# MEASUREMENT.net
KiCad netlist of a schematic drawn in Altium Designer
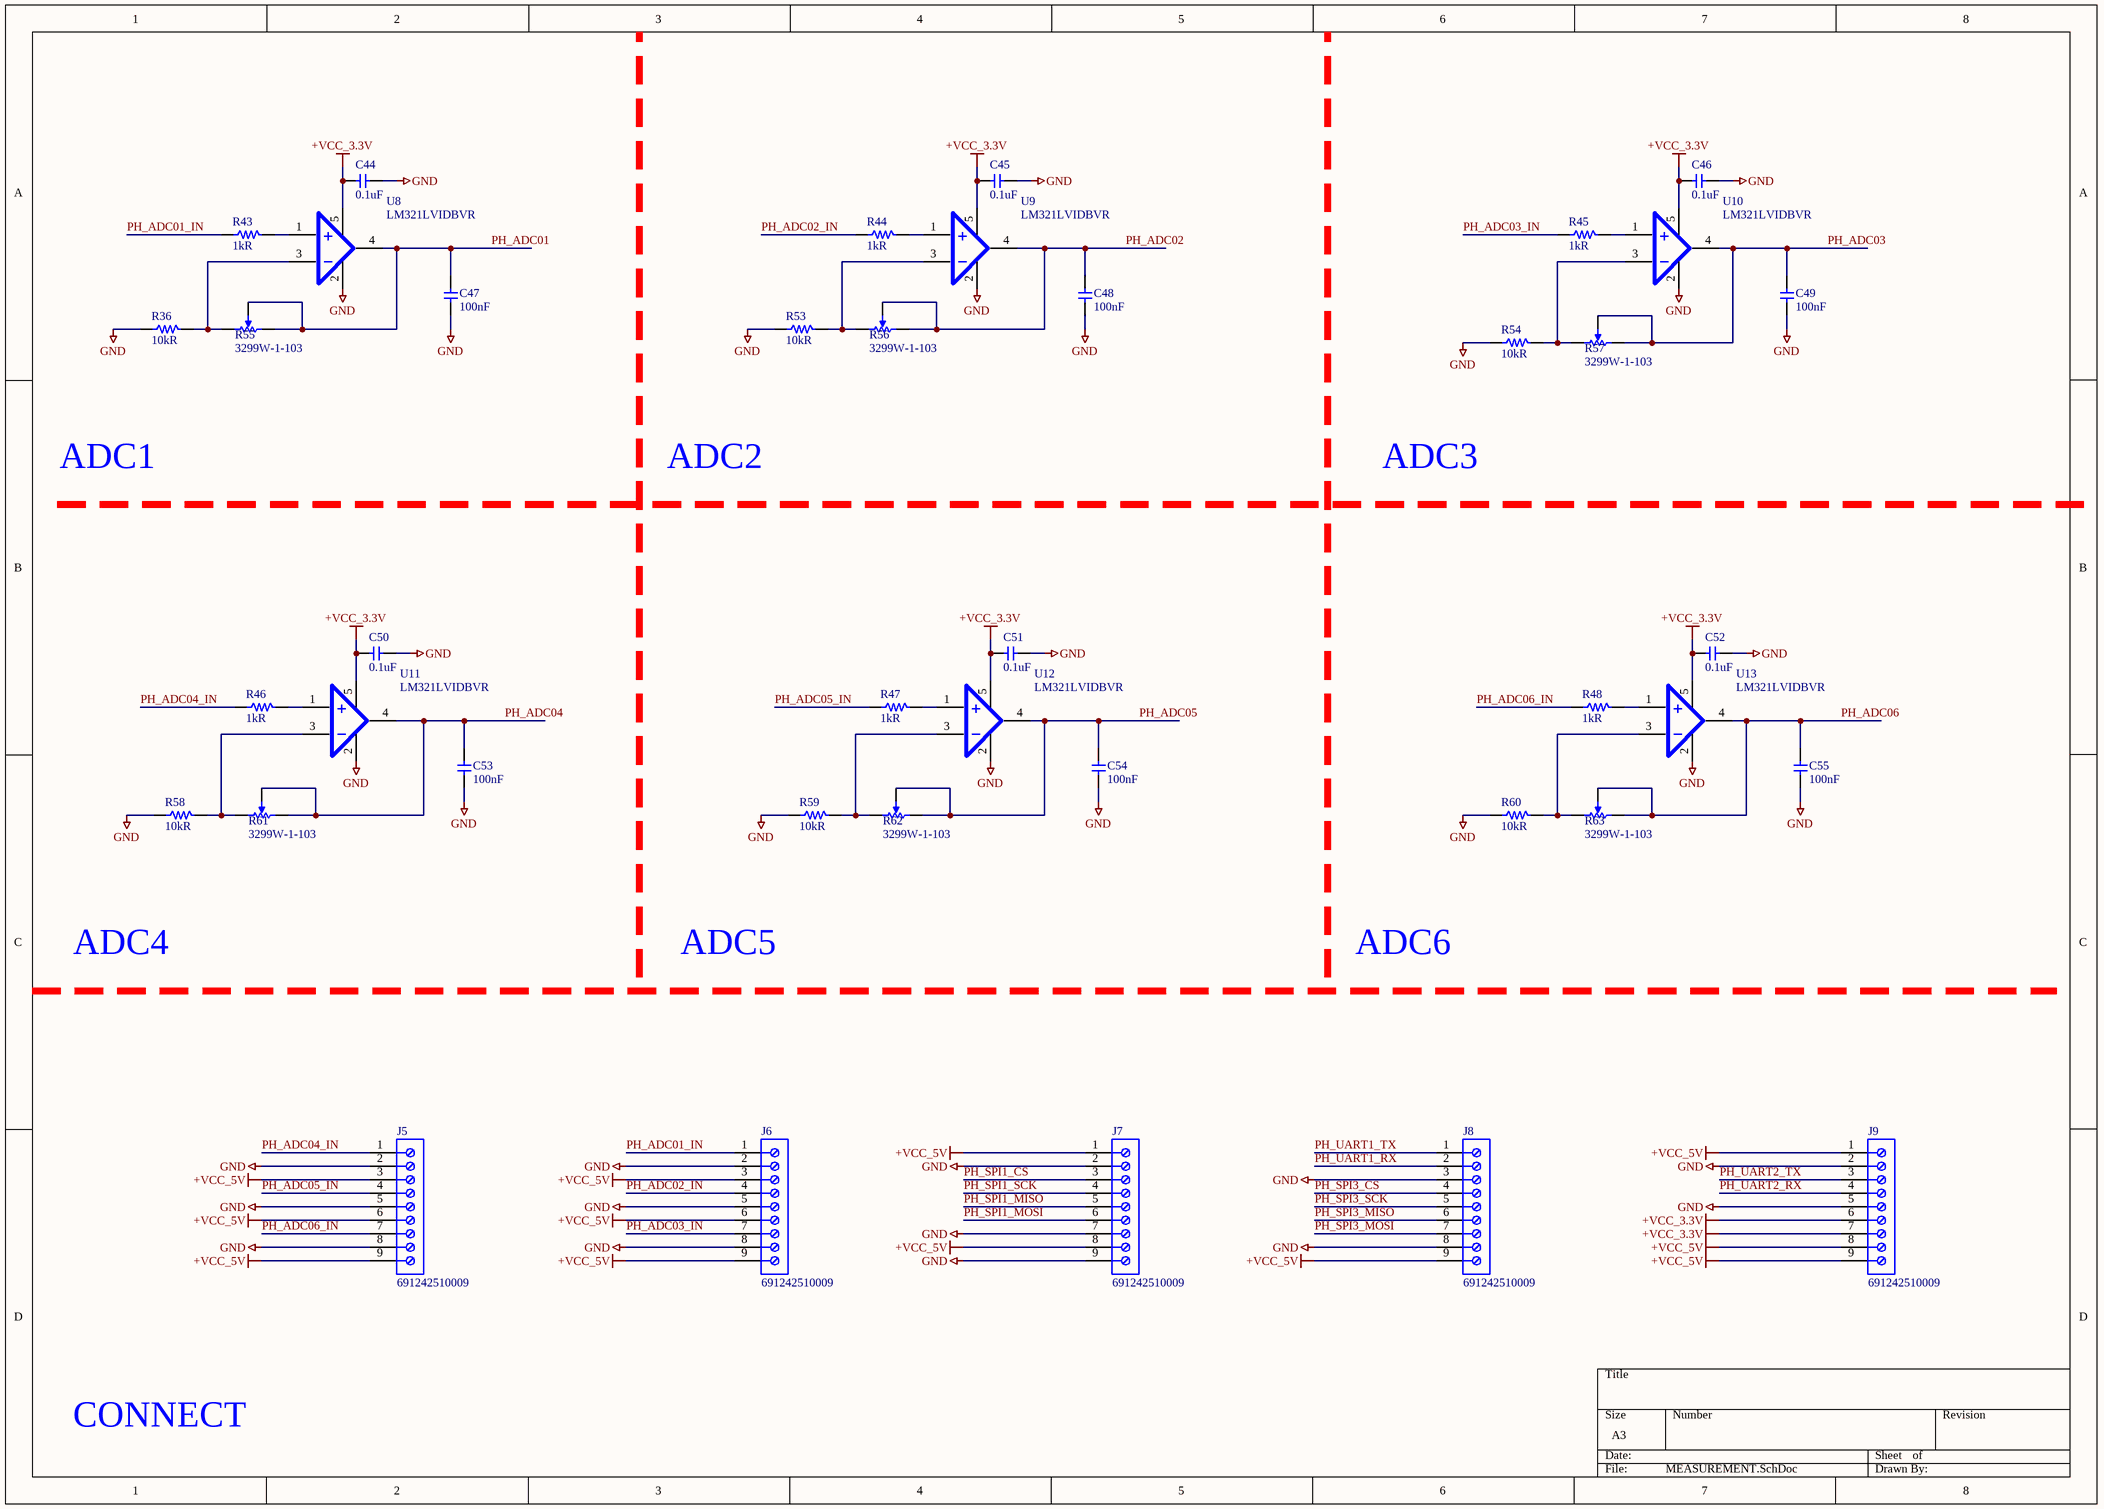
[diagram p0: MEASUREMENT.SchDoc]

(export (version "E")
  (design (tool "Eeschema 10.0.6"))
  (components
    (comp (ref "C44")
      (value "0.1uF")
      (footprint "CAP 0402 (1005)")
      (description "50V 100nF ±10% 0402 Multilayer Ceramic Capacitors MLCC - SMD/SMT ROHS")
      (fields
        (field (name "MANUFACTURER") "Samwha Capacitor")
        (field (name "MANUFACTURER PART NUMBER") "CS1005X7R104K500NR")
      )
      (libsource (lib "BSR NODE_V2.0 LIB") (part "CAP0402 0.1uF 50V"))
    )
    (comp (ref "C45")
      (value "0.1uF")
      (footprint "CAP 0402 (1005)")
      (description "50V 100nF ±10% 0402 Multilayer Ceramic Capacitors MLCC - SMD/SMT ROHS")
      (fields
        (field (name "MANUFACTURER") "Samwha Capacitor")
        (field (name "MANUFACTURER PART NUMBER") "CS1005X7R104K500NR")
      )
      (libsource (lib "BSR NODE_V2.0 LIB") (part "CAP0402 0.1uF 50V"))
    )
    (comp (ref "C46")
      (value "0.1uF")
      (footprint "CAP 0402 (1005)")
      (description "50V 100nF ±10% 0402 Multilayer Ceramic Capacitors MLCC - SMD/SMT ROHS")
      (fields
        (field (name "MANUFACTURER") "Samwha Capacitor")
        (field (name "MANUFACTURER PART NUMBER") "CS1005X7R104K500NR")
      )
      (libsource (lib "BSR NODE_V2.0 LIB") (part "CAP0402 0.1uF 50V"))
    )
    (comp (ref "C47")
      (value "100nF")
      (footprint "CAP 0402 (1005)")
      (description "50V 100nF ±10% 0402 Multilayer Ceramic Capacitors MLCC - SMD/SMT ROHS")
      (fields
        (field (name "MANUFACTURER") "Samwha Capacitor")
        (field (name "MANUFACTURER PART NUMBER") "CS1005X7R104K500NR")
      )
      (libsource (lib "BSR NODE_V2.0 LIB") (part "CAP0402 0.1uF 50V"))
    )
    (comp (ref "C48")
      (value "100nF")
      (footprint "CAP 0402 (1005)")
      (description "50V 100nF ±10% 0402 Multilayer Ceramic Capacitors MLCC - SMD/SMT ROHS")
      (fields
        (field (name "MANUFACTURER") "Samwha Capacitor")
        (field (name "MANUFACTURER PART NUMBER") "CS1005X7R104K500NR")
      )
      (libsource (lib "BSR NODE_V2.0 LIB") (part "CAP0402 0.1uF 50V"))
    )
    (comp (ref "C49")
      (value "100nF")
      (footprint "CAP 0402 (1005)")
      (description "50V 100nF ±10% 0402 Multilayer Ceramic Capacitors MLCC - SMD/SMT ROHS")
      (fields
        (field (name "MANUFACTURER") "Samwha Capacitor")
        (field (name "MANUFACTURER PART NUMBER") "CS1005X7R104K500NR")
      )
      (libsource (lib "BSR NODE_V2.0 LIB") (part "CAP0402 0.1uF 50V"))
    )
    (comp (ref "C50")
      (value "0.1uF")
      (footprint "CAP 0402 (1005)")
      (description "50V 100nF ±10% 0402 Multilayer Ceramic Capacitors MLCC - SMD/SMT ROHS")
      (fields
        (field (name "MANUFACTURER") "Samwha Capacitor")
        (field (name "MANUFACTURER PART NUMBER") "CS1005X7R104K500NR")
      )
      (libsource (lib "BSR NODE_V2.0 LIB") (part "CAP0402 0.1uF 50V"))
    )
    (comp (ref "C51")
      (value "0.1uF")
      (footprint "CAP 0402 (1005)")
      (description "50V 100nF ±10% 0402 Multilayer Ceramic Capacitors MLCC - SMD/SMT ROHS")
      (fields
        (field (name "MANUFACTURER") "Samwha Capacitor")
        (field (name "MANUFACTURER PART NUMBER") "CS1005X7R104K500NR")
      )
      (libsource (lib "BSR NODE_V2.0 LIB") (part "CAP0402 0.1uF 50V"))
    )
    (comp (ref "C52")
      (value "0.1uF")
      (footprint "CAP 0402 (1005)")
      (description "50V 100nF ±10% 0402 Multilayer Ceramic Capacitors MLCC - SMD/SMT ROHS")
      (fields
        (field (name "MANUFACTURER") "Samwha Capacitor")
        (field (name "MANUFACTURER PART NUMBER") "CS1005X7R104K500NR")
      )
      (libsource (lib "BSR NODE_V2.0 LIB") (part "CAP0402 0.1uF 50V"))
    )
    (comp (ref "C53")
      (value "100nF")
      (footprint "CAP 0402 (1005)")
      (description "50V 100nF ±10% 0402 Multilayer Ceramic Capacitors MLCC - SMD/SMT ROHS")
      (fields
        (field (name "MANUFACTURER") "Samwha Capacitor")
        (field (name "MANUFACTURER PART NUMBER") "CS1005X7R104K500NR")
      )
      (libsource (lib "BSR NODE_V2.0 LIB") (part "CAP0402 0.1uF 50V"))
    )
    (comp (ref "C54")
      (value "100nF")
      (footprint "CAP 0402 (1005)")
      (description "50V 100nF ±10% 0402 Multilayer Ceramic Capacitors MLCC - SMD/SMT ROHS")
      (fields
        (field (name "MANUFACTURER") "Samwha Capacitor")
        (field (name "MANUFACTURER PART NUMBER") "CS1005X7R104K500NR")
      )
      (libsource (lib "BSR NODE_V2.0 LIB") (part "CAP0402 0.1uF 50V"))
    )
    (comp (ref "C55")
      (value "100nF")
      (footprint "CAP 0402 (1005)")
      (description "50V 100nF ±10% 0402 Multilayer Ceramic Capacitors MLCC - SMD/SMT ROHS")
      (fields
        (field (name "MANUFACTURER") "Samwha Capacitor")
        (field (name "MANUFACTURER PART NUMBER") "CS1005X7R104K500NR")
      )
      (libsource (lib "BSR NODE_V2.0 LIB") (part "CAP0402 0.1uF 50V"))
    )
    (comp (ref "J5")
      (value "691242510009")
      (footprint "691242510009")
      (description "Terminal Block, 5.08MM Pitch, Horizontal, Rising Cage Clamp, 12-30 AWG, 9 Pin")
      (libsource (lib "Altium Content Vault") (part "TBL - 1R - 09P - Screw"))
    )
    (comp (ref "J6")
      (value "691242510009")
      (footprint "691242510009")
      (description "Terminal Block, 5.08MM Pitch, Horizontal, Rising Cage Clamp, 12-30 AWG, 9 Pin")
      (libsource (lib "Altium Content Vault") (part "TBL - 1R - 09P - Screw"))
    )
    (comp (ref "J7")
      (value "691242510009")
      (footprint "691242510009")
      (description "Terminal Block, 5.08MM Pitch, Horizontal, Rising Cage Clamp, 12-30 AWG, 9 Pin")
      (libsource (lib "Altium Content Vault") (part "TBL - 1R - 09P - Screw"))
    )
    (comp (ref "J8")
      (value "691242510009")
      (footprint "691242510009")
      (description "Terminal Block, 5.08MM Pitch, Horizontal, Rising Cage Clamp, 12-30 AWG, 9 Pin")
      (libsource (lib "Altium Content Vault") (part "TBL - 1R - 09P - Screw"))
    )
    (comp (ref "J9")
      (value "691242510009")
      (footprint "691242510009")
      (description "Terminal Block, 5.08MM Pitch, Horizontal, Rising Cage Clamp, 12-30 AWG, 9 Pin")
      (libsource (lib "Altium Content Vault") (part "TBL - 1R - 09P - Screw"))
    )
    (comp (ref "R36")
      (value "10kR")
      (footprint "RES 0402 (1005)")
      (description "±1% 10kΩ 0402 Chip Resistor - Surface Mount ROHS")
      (fields (field (name "MANUFACTURER") "VO") (field (name "MANUFACTURER PART NUMBER") "SCR0402F10K"))
      (libsource (lib "BSR NODE_V2.0 LIB") (part "RES0402 10kR 1%"))
    )
    (comp (ref "R43")
      (value "1kR")
      (footprint "RES 0402 (1005)")
      (description "±1% 10kΩ 0402 Chip Resistor - Surface Mount ROHS")
      (fields (field (name "MANUFACTURER") "VO") (field (name "MANUFACTURER PART NUMBER") "SCR0402F10K"))
      (libsource (lib "BSR NODE_V2.0 LIB") (part "RES0402 10kR 1%"))
    )
    (comp (ref "R44")
      (value "1kR")
      (footprint "RES 0402 (1005)")
      (description "±1% 10kΩ 0402 Chip Resistor - Surface Mount ROHS")
      (fields (field (name "MANUFACTURER") "VO") (field (name "MANUFACTURER PART NUMBER") "SCR0402F10K"))
      (libsource (lib "BSR NODE_V2.0 LIB") (part "RES0402 10kR 1%"))
    )
    (comp (ref "R45")
      (value "1kR")
      (footprint "RES 0402 (1005)")
      (description "±1% 10kΩ 0402 Chip Resistor - Surface Mount ROHS")
      (fields (field (name "MANUFACTURER") "VO") (field (name "MANUFACTURER PART NUMBER") "SCR0402F10K"))
      (libsource (lib "BSR NODE_V2.0 LIB") (part "RES0402 10kR 1%"))
    )
    (comp (ref "R46")
      (value "1kR")
      (footprint "RES 0402 (1005)")
      (description "±1% 10kΩ 0402 Chip Resistor - Surface Mount ROHS")
      (fields (field (name "MANUFACTURER") "VO") (field (name "MANUFACTURER PART NUMBER") "SCR0402F10K"))
      (libsource (lib "BSR NODE_V2.0 LIB") (part "RES0402 10kR 1%"))
    )
    (comp (ref "R47")
      (value "1kR")
      (footprint "RES 0402 (1005)")
      (description "±1% 10kΩ 0402 Chip Resistor - Surface Mount ROHS")
      (fields (field (name "MANUFACTURER") "VO") (field (name "MANUFACTURER PART NUMBER") "SCR0402F10K"))
      (libsource (lib "BSR NODE_V2.0 LIB") (part "RES0402 10kR 1%"))
    )
    (comp (ref "R48")
      (value "1kR")
      (footprint "RES 0402 (1005)")
      (description "±1% 10kΩ 0402 Chip Resistor - Surface Mount ROHS")
      (fields (field (name "MANUFACTURER") "VO") (field (name "MANUFACTURER PART NUMBER") "SCR0402F10K"))
      (libsource (lib "BSR NODE_V2.0 LIB") (part "RES0402 10kR 1%"))
    )
    (comp (ref "R53")
      (value "10kR")
      (footprint "RES 0402 (1005)")
      (description "±1% 10kΩ 0402 Chip Resistor - Surface Mount ROHS")
      (fields (field (name "MANUFACTURER") "VO") (field (name "MANUFACTURER PART NUMBER") "SCR0402F10K"))
      (libsource (lib "BSR NODE_V2.0 LIB") (part "RES0402 10kR 1%"))
    )
    (comp (ref "R54")
      (value "10kR")
      (footprint "RES 0402 (1005)")
      (description "±1% 10kΩ 0402 Chip Resistor - Surface Mount ROHS")
      (fields (field (name "MANUFACTURER") "VO") (field (name "MANUFACTURER PART NUMBER") "SCR0402F10K"))
      (libsource (lib "BSR NODE_V2.0 LIB") (part "RES0402 10kR 1%"))
    )
    (comp (ref "R55")
      (value "3299W-1-103")
      (footprint "BOUR-3299W-3_V")
      (fields (field (name "MANUFACTURER") "Bourns") (field (name "TOLERANCE") "10%"))
      (libsource (lib "Altium Content Vault") (part "RES-ADJ-3_A"))
    )
    (comp (ref "R56")
      (value "3299W-1-103")
      (footprint "BOUR-3299W-3_V")
      (fields (field (name "MANUFACTURER") "Bourns") (field (name "TOLERANCE") "10%"))
      (libsource (lib "Altium Content Vault") (part "RES-ADJ-3_A"))
    )
    (comp (ref "R57")
      (value "3299W-1-103")
      (footprint "BOUR-3299W-3_V")
      (fields (field (name "MANUFACTURER") "Bourns") (field (name "TOLERANCE") "10%"))
      (libsource (lib "Altium Content Vault") (part "RES-ADJ-3_A"))
    )
    (comp (ref "R58")
      (value "10kR")
      (footprint "RES 0402 (1005)")
      (description "±1% 10kΩ 0402 Chip Resistor - Surface Mount ROHS")
      (fields (field (name "MANUFACTURER") "VO") (field (name "MANUFACTURER PART NUMBER") "SCR0402F10K"))
      (libsource (lib "BSR NODE_V2.0 LIB") (part "RES0402 10kR 1%"))
    )
    (comp (ref "R59")
      (value "10kR")
      (footprint "RES 0402 (1005)")
      (description "±1% 10kΩ 0402 Chip Resistor - Surface Mount ROHS")
      (fields (field (name "MANUFACTURER") "VO") (field (name "MANUFACTURER PART NUMBER") "SCR0402F10K"))
      (libsource (lib "BSR NODE_V2.0 LIB") (part "RES0402 10kR 1%"))
    )
    (comp (ref "R60")
      (value "10kR")
      (footprint "RES 0402 (1005)")
      (description "±1% 10kΩ 0402 Chip Resistor - Surface Mount ROHS")
      (fields (field (name "MANUFACTURER") "VO") (field (name "MANUFACTURER PART NUMBER") "SCR0402F10K"))
      (libsource (lib "BSR NODE_V2.0 LIB") (part "RES0402 10kR 1%"))
    )
    (comp (ref "R61")
      (value "3299W-1-103")
      (footprint "BOUR-3299W-3_V")
      (fields (field (name "MANUFACTURER") "Bourns") (field (name "TOLERANCE") "10%"))
      (libsource (lib "Altium Content Vault") (part "RES-ADJ-3_A"))
    )
    (comp (ref "R62")
      (value "3299W-1-103")
      (footprint "BOUR-3299W-3_V")
      (fields (field (name "MANUFACTURER") "Bourns") (field (name "TOLERANCE") "10%"))
      (libsource (lib "Altium Content Vault") (part "RES-ADJ-3_A"))
    )
    (comp (ref "R63")
      (value "3299W-1-103")
      (footprint "BOUR-3299W-3_V")
      (fields (field (name "MANUFACTURER") "Bourns") (field (name "TOLERANCE") "10%"))
      (libsource (lib "Altium Content Vault") (part "RES-ADJ-3_A"))
    )
    (comp (ref "U8")
      (value "LM321LVIDBVR")
      (footprint "SOT-23-5")
      (description "IC OPAMP GP 1 CIRCUIT SOT23-5")
      (fields (field (name "MANUFACTURER") "Texas Instruments"))
      (libsource (lib "BSR") (part "IC OPAM LM321LVIDBVR"))
    )
    (comp (ref "U9")
      (value "LM321LVIDBVR")
      (footprint "SOT-23-5")
      (description "IC OPAMP GP 1 CIRCUIT SOT23-5")
      (fields (field (name "MANUFACTURER") "Texas Instruments"))
      (libsource (lib "BSR") (part "IC OPAM LM321LVIDBVR"))
    )
    (comp (ref "U10")
      (value "LM321LVIDBVR")
      (footprint "SOT-23-5")
      (description "IC OPAMP GP 1 CIRCUIT SOT23-5")
      (fields (field (name "MANUFACTURER") "Texas Instruments"))
      (libsource (lib "BSR") (part "IC OPAM LM321LVIDBVR"))
    )
    (comp (ref "U11")
      (value "LM321LVIDBVR")
      (footprint "SOT-23-5")
      (description "IC OPAMP GP 1 CIRCUIT SOT23-5")
      (fields (field (name "MANUFACTURER") "Texas Instruments"))
      (libsource (lib "BSR") (part "IC OPAM LM321LVIDBVR"))
    )
    (comp (ref "U12")
      (value "LM321LVIDBVR")
      (footprint "SOT-23-5")
      (description "IC OPAMP GP 1 CIRCUIT SOT23-5")
      (fields (field (name "MANUFACTURER") "Texas Instruments"))
      (libsource (lib "BSR") (part "IC OPAM LM321LVIDBVR"))
    )
    (comp (ref "U13")
      (value "LM321LVIDBVR")
      (footprint "SOT-23-5")
      (description "IC OPAMP GP 1 CIRCUIT SOT23-5")
      (fields (field (name "MANUFACTURER") "Texas Instruments"))
      (libsource (lib "BSR") (part "IC OPAM LM321LVIDBVR"))
    )
  )
  (nets
    (net (code "1") (name "+VCC_3.3V") (class "Default")
      (node (ref "C44") (pin "2") (pinfunction "2_2") (pintype "passive"))
      (node (ref "C45") (pin "2") (pinfunction "2_2") (pintype "passive"))
      (node (ref "C46") (pin "2") (pinfunction "2_2") (pintype "passive"))
      (node (ref "C50") (pin "2") (pinfunction "2_2") (pintype "passive"))
      (node (ref "C51") (pin "2") (pinfunction "2_2") (pintype "passive"))
      (node (ref "C52") (pin "2") (pinfunction "2_2") (pintype "passive"))
      (node (ref "J9") (pin "6") (pinfunction "6_6") (pintype "passive"))
      (node (ref "J9") (pin "7") (pinfunction "7_7") (pintype "passive"))
      (node (ref "U10") (pin "5") (pinfunction "5_5") (pintype "passive"))
      (node (ref "U11") (pin "5") (pinfunction "5_5") (pintype "passive"))
      (node (ref "U12") (pin "5") (pinfunction "5_5") (pintype "passive"))
      (node (ref "U13") (pin "5") (pinfunction "5_5") (pintype "passive"))
      (node (ref "U8") (pin "5") (pinfunction "5_5") (pintype "passive"))
      (node (ref "U9") (pin "5") (pinfunction "5_5") (pintype "passive"))
    )
    (net (code "2") (name "+VCC_5V") (class "Default")
      (node (ref "J5") (pin "3") (pinfunction "3_3") (pintype "passive"))
      (node (ref "J5") (pin "6") (pinfunction "6_6") (pintype "passive"))
      (node (ref "J5") (pin "9") (pinfunction "9_9") (pintype "passive"))
      (node (ref "J6") (pin "3") (pinfunction "3_3") (pintype "passive"))
      (node (ref "J6") (pin "6") (pinfunction "6_6") (pintype "passive"))
      (node (ref "J6") (pin "9") (pinfunction "9_9") (pintype "passive"))
      (node (ref "J7") (pin "1") (pinfunction "1_1") (pintype "passive"))
      (node (ref "J7") (pin "8") (pinfunction "8_8") (pintype "passive"))
      (node (ref "J8") (pin "9") (pinfunction "9_9") (pintype "passive"))
      (node (ref "J9") (pin "1") (pinfunction "1_1") (pintype "passive"))
      (node (ref "J9") (pin "8") (pinfunction "8_8") (pintype "passive"))
      (node (ref "J9") (pin "9") (pinfunction "9_9") (pintype "passive"))
    )
    (net (code "3") (name "/PH_ADC01") (class "Default")
      (node (ref "C47") (pin "2") (pinfunction "2_2") (pintype "passive"))
      (node (ref "R55") (pin "1") (pinfunction "1_1") (pintype "passive"))
      (node (ref "R55") (pin "2") (pinfunction "2_2") (pintype "passive"))
      (node (ref "U8") (pin "4") (pinfunction "4_4") (pintype "passive"))
    )
    (net (code "4") (name "/PH_ADC01_IN") (class "Default")
      (node (ref "J6") (pin "1") (pinfunction "1_1") (pintype "passive"))
      (node (ref "R43") (pin "2") (pinfunction "2_2") (pintype "passive"))
    )
    (net (code "5") (name "/PH_ADC02") (class "Default")
      (node (ref "C48") (pin "2") (pinfunction "2_2") (pintype "passive"))
      (node (ref "R56") (pin "1") (pinfunction "1_1") (pintype "passive"))
      (node (ref "R56") (pin "2") (pinfunction "2_2") (pintype "passive"))
      (node (ref "U9") (pin "4") (pinfunction "4_4") (pintype "passive"))
    )
    (net (code "6") (name "/PH_ADC02_IN") (class "Default")
      (node (ref "J6") (pin "4") (pinfunction "4_4") (pintype "passive"))
      (node (ref "R44") (pin "2") (pinfunction "2_2") (pintype "passive"))
    )
    (net (code "7") (name "/PH_ADC03") (class "Default")
      (node (ref "C49") (pin "2") (pinfunction "2_2") (pintype "passive"))
      (node (ref "R57") (pin "1") (pinfunction "1_1") (pintype "passive"))
      (node (ref "R57") (pin "2") (pinfunction "2_2") (pintype "passive"))
      (node (ref "U10") (pin "4") (pinfunction "4_4") (pintype "passive"))
    )
    (net (code "8") (name "/PH_ADC03_IN") (class "Default")
      (node (ref "J6") (pin "7") (pinfunction "7_7") (pintype "passive"))
      (node (ref "R45") (pin "2") (pinfunction "2_2") (pintype "passive"))
    )
    (net (code "9") (name "/PH_ADC04") (class "Default")
      (node (ref "C53") (pin "2") (pinfunction "2_2") (pintype "passive"))
      (node (ref "R61") (pin "1") (pinfunction "1_1") (pintype "passive"))
      (node (ref "R61") (pin "2") (pinfunction "2_2") (pintype "passive"))
      (node (ref "U11") (pin "4") (pinfunction "4_4") (pintype "passive"))
    )
    (net (code "10") (name "/PH_ADC04_IN") (class "Default")
      (node (ref "J5") (pin "1") (pinfunction "1_1") (pintype "passive"))
      (node (ref "R46") (pin "2") (pinfunction "2_2") (pintype "passive"))
    )
    (net (code "11") (name "/PH_ADC05") (class "Default")
      (node (ref "C54") (pin "2") (pinfunction "2_2") (pintype "passive"))
      (node (ref "R62") (pin "1") (pinfunction "1_1") (pintype "passive"))
      (node (ref "R62") (pin "2") (pinfunction "2_2") (pintype "passive"))
      (node (ref "U12") (pin "4") (pinfunction "4_4") (pintype "passive"))
    )
    (net (code "12") (name "/PH_ADC05_IN") (class "Default")
      (node (ref "J5") (pin "4") (pinfunction "4_4") (pintype "passive"))
      (node (ref "R47") (pin "2") (pinfunction "2_2") (pintype "passive"))
    )
    (net (code "13") (name "/PH_ADC06") (class "Default")
      (node (ref "C55") (pin "2") (pinfunction "2_2") (pintype "passive"))
      (node (ref "R63") (pin "1") (pinfunction "1_1") (pintype "passive"))
      (node (ref "R63") (pin "2") (pinfunction "2_2") (pintype "passive"))
      (node (ref "U13") (pin "4") (pinfunction "4_4") (pintype "passive"))
    )
    (net (code "14") (name "/PH_ADC06_IN") (class "Default")
      (node (ref "J5") (pin "7") (pinfunction "7_7") (pintype "passive"))
      (node (ref "R48") (pin "2") (pinfunction "2_2") (pintype "passive"))
    )
    (net (code "15") (name "/PH_SPI1_CS") (class "Default")
      (node (ref "J7") (pin "3") (pinfunction "3_3") (pintype "passive"))
    )
    (net (code "16") (name "/PH_SPI1_MISO") (class "Default")
      (node (ref "J7") (pin "5") (pinfunction "5_5") (pintype "passive"))
    )
    (net (code "17") (name "/PH_SPI1_MOSI") (class "Default")
      (node (ref "J7") (pin "6") (pinfunction "6_6") (pintype "passive"))
    )
    (net (code "18") (name "/PH_SPI1_SCK") (class "Default")
      (node (ref "J7") (pin "4") (pinfunction "4_4") (pintype "passive"))
    )
    (net (code "19") (name "/PH_SPI3_CS") (class "Default")
      (node (ref "J8") (pin "4") (pinfunction "4_4") (pintype "passive"))
    )
    (net (code "20") (name "/PH_SPI3_MISO") (class "Default")
      (node (ref "J8") (pin "6") (pinfunction "6_6") (pintype "passive"))
    )
    (net (code "21") (name "/PH_SPI3_MOSI") (class "Default")
      (node (ref "J8") (pin "7") (pinfunction "7_7") (pintype "passive"))
    )
    (net (code "22") (name "/PH_SPI3_SCK") (class "Default")
      (node (ref "J8") (pin "5") (pinfunction "5_5") (pintype "passive"))
    )
    (net (code "23") (name "/PH_UART1_RX") (class "Default")
      (node (ref "J8") (pin "2") (pinfunction "2_2") (pintype "passive"))
    )
    (net (code "24") (name "/PH_UART1_TX") (class "Default")
      (node (ref "J8") (pin "1") (pinfunction "1_1") (pintype "passive"))
    )
    (net (code "25") (name "/PH_UART2_RX") (class "Default")
      (node (ref "J9") (pin "4") (pinfunction "4_4") (pintype "passive"))
    )
    (net (code "26") (name "/PH_UART2_TX") (class "Default")
      (node (ref "J9") (pin "3") (pinfunction "3_3") (pintype "passive"))
    )
    (net (code "27") (name "GND") (class "Default")
      (node (ref "C44") (pin "1") (pinfunction "1_1") (pintype "passive"))
      (node (ref "C45") (pin "1") (pinfunction "1_1") (pintype "passive"))
      (node (ref "C46") (pin "1") (pinfunction "1_1") (pintype "passive"))
      (node (ref "C47") (pin "1") (pinfunction "1_1") (pintype "passive"))
      (node (ref "C48") (pin "1") (pinfunction "1_1") (pintype "passive"))
      (node (ref "C49") (pin "1") (pinfunction "1_1") (pintype "passive"))
      (node (ref "C50") (pin "1") (pinfunction "1_1") (pintype "passive"))
      (node (ref "C51") (pin "1") (pinfunction "1_1") (pintype "passive"))
      (node (ref "C52") (pin "1") (pinfunction "1_1") (pintype "passive"))
      (node (ref "C53") (pin "1") (pinfunction "1_1") (pintype "passive"))
      (node (ref "C54") (pin "1") (pinfunction "1_1") (pintype "passive"))
      (node (ref "C55") (pin "1") (pinfunction "1_1") (pintype "passive"))
      (node (ref "J5") (pin "2") (pinfunction "2_2") (pintype "passive"))
      (node (ref "J5") (pin "5") (pinfunction "5_5") (pintype "passive"))
      (node (ref "J5") (pin "8") (pinfunction "8_8") (pintype "passive"))
      (node (ref "J6") (pin "2") (pinfunction "2_2") (pintype "passive"))
      (node (ref "J6") (pin "5") (pinfunction "5_5") (pintype "passive"))
      (node (ref "J6") (pin "8") (pinfunction "8_8") (pintype "passive"))
      (node (ref "J7") (pin "2") (pinfunction "2_2") (pintype "passive"))
      (node (ref "J7") (pin "7") (pinfunction "7_7") (pintype "passive"))
      (node (ref "J7") (pin "9") (pinfunction "9_9") (pintype "passive"))
      (node (ref "J8") (pin "3") (pinfunction "3_3") (pintype "passive"))
      (node (ref "J8") (pin "8") (pinfunction "8_8") (pintype "passive"))
      (node (ref "J9") (pin "2") (pinfunction "2_2") (pintype "passive"))
      (node (ref "J9") (pin "5") (pinfunction "5_5") (pintype "passive"))
      (node (ref "R36") (pin "2") (pinfunction "2_2") (pintype "passive"))
      (node (ref "R53") (pin "2") (pinfunction "2_2") (pintype "passive"))
      (node (ref "R54") (pin "2") (pinfunction "2_2") (pintype "passive"))
      (node (ref "R58") (pin "2") (pinfunction "2_2") (pintype "passive"))
      (node (ref "R59") (pin "2") (pinfunction "2_2") (pintype "passive"))
      (node (ref "R60") (pin "2") (pinfunction "2_2") (pintype "passive"))
      (node (ref "U10") (pin "2") (pinfunction "2_2") (pintype "passive"))
      (node (ref "U11") (pin "2") (pinfunction "2_2") (pintype "passive"))
      (node (ref "U12") (pin "2") (pinfunction "2_2") (pintype "passive"))
      (node (ref "U13") (pin "2") (pinfunction "2_2") (pintype "passive"))
      (node (ref "U8") (pin "2") (pinfunction "2_2") (pintype "passive"))
      (node (ref "U9") (pin "2") (pinfunction "2_2") (pintype "passive"))
    )
    (net (code "28") (name "Net-(R36-Pad1)") (class "Default")
      (node (ref "R36") (pin "1") (pinfunction "1_1") (pintype "passive"))
      (node (ref "R55") (pin "3") (pinfunction "3_3") (pintype "passive"))
      (node (ref "U8") (pin "3") (pinfunction "3_3") (pintype "passive"))
    )
    (net (code "29") (name "Net-(R43-Pad1)") (class "Default")
      (node (ref "R43") (pin "1") (pinfunction "1_1") (pintype "passive"))
      (node (ref "U8") (pin "1") (pinfunction "1_1") (pintype "passive"))
    )
    (net (code "30") (name "Net-(R44-Pad1)") (class "Default")
      (node (ref "R44") (pin "1") (pinfunction "1_1") (pintype "passive"))
      (node (ref "U9") (pin "1") (pinfunction "1_1") (pintype "passive"))
    )
    (net (code "31") (name "Net-(R45-Pad1)") (class "Default")
      (node (ref "R45") (pin "1") (pinfunction "1_1") (pintype "passive"))
      (node (ref "U10") (pin "1") (pinfunction "1_1") (pintype "passive"))
    )
    (net (code "32") (name "Net-(R46-Pad1)") (class "Default")
      (node (ref "R46") (pin "1") (pinfunction "1_1") (pintype "passive"))
      (node (ref "U11") (pin "1") (pinfunction "1_1") (pintype "passive"))
    )
    (net (code "33") (name "Net-(R47-Pad1)") (class "Default")
      (node (ref "R47") (pin "1") (pinfunction "1_1") (pintype "passive"))
      (node (ref "U12") (pin "1") (pinfunction "1_1") (pintype "passive"))
    )
    (net (code "34") (name "Net-(R48-Pad1)") (class "Default")
      (node (ref "R48") (pin "1") (pinfunction "1_1") (pintype "passive"))
      (node (ref "U13") (pin "1") (pinfunction "1_1") (pintype "passive"))
    )
    (net (code "35") (name "Net-(R53-Pad1)") (class "Default")
      (node (ref "R53") (pin "1") (pinfunction "1_1") (pintype "passive"))
      (node (ref "R56") (pin "3") (pinfunction "3_3") (pintype "passive"))
      (node (ref "U9") (pin "3") (pinfunction "3_3") (pintype "passive"))
    )
    (net (code "36") (name "Net-(R54-Pad1)") (class "Default")
      (node (ref "R54") (pin "1") (pinfunction "1_1") (pintype "passive"))
      (node (ref "R57") (pin "3") (pinfunction "3_3") (pintype "passive"))
      (node (ref "U10") (pin "3") (pinfunction "3_3") (pintype "passive"))
    )
    (net (code "37") (name "Net-(R58-Pad1)") (class "Default")
      (node (ref "R58") (pin "1") (pinfunction "1_1") (pintype "passive"))
      (node (ref "R61") (pin "3") (pinfunction "3_3") (pintype "passive"))
      (node (ref "U11") (pin "3") (pinfunction "3_3") (pintype "passive"))
    )
    (net (code "38") (name "Net-(R59-Pad1)") (class "Default")
      (node (ref "R59") (pin "1") (pinfunction "1_1") (pintype "passive"))
      (node (ref "R62") (pin "3") (pinfunction "3_3") (pintype "passive"))
      (node (ref "U12") (pin "3") (pinfunction "3_3") (pintype "passive"))
    )
    (net (code "39") (name "Net-(R60-Pad1)") (class "Default")
      (node (ref "R60") (pin "1") (pinfunction "1_1") (pintype "passive"))
      (node (ref "R63") (pin "3") (pinfunction "3_3") (pintype "passive"))
      (node (ref "U13") (pin "3") (pinfunction "3_3") (pintype "passive"))
    )
  )
)
